# SController-8833.net
KiCad netlist of a schematic drawn in EAGLE
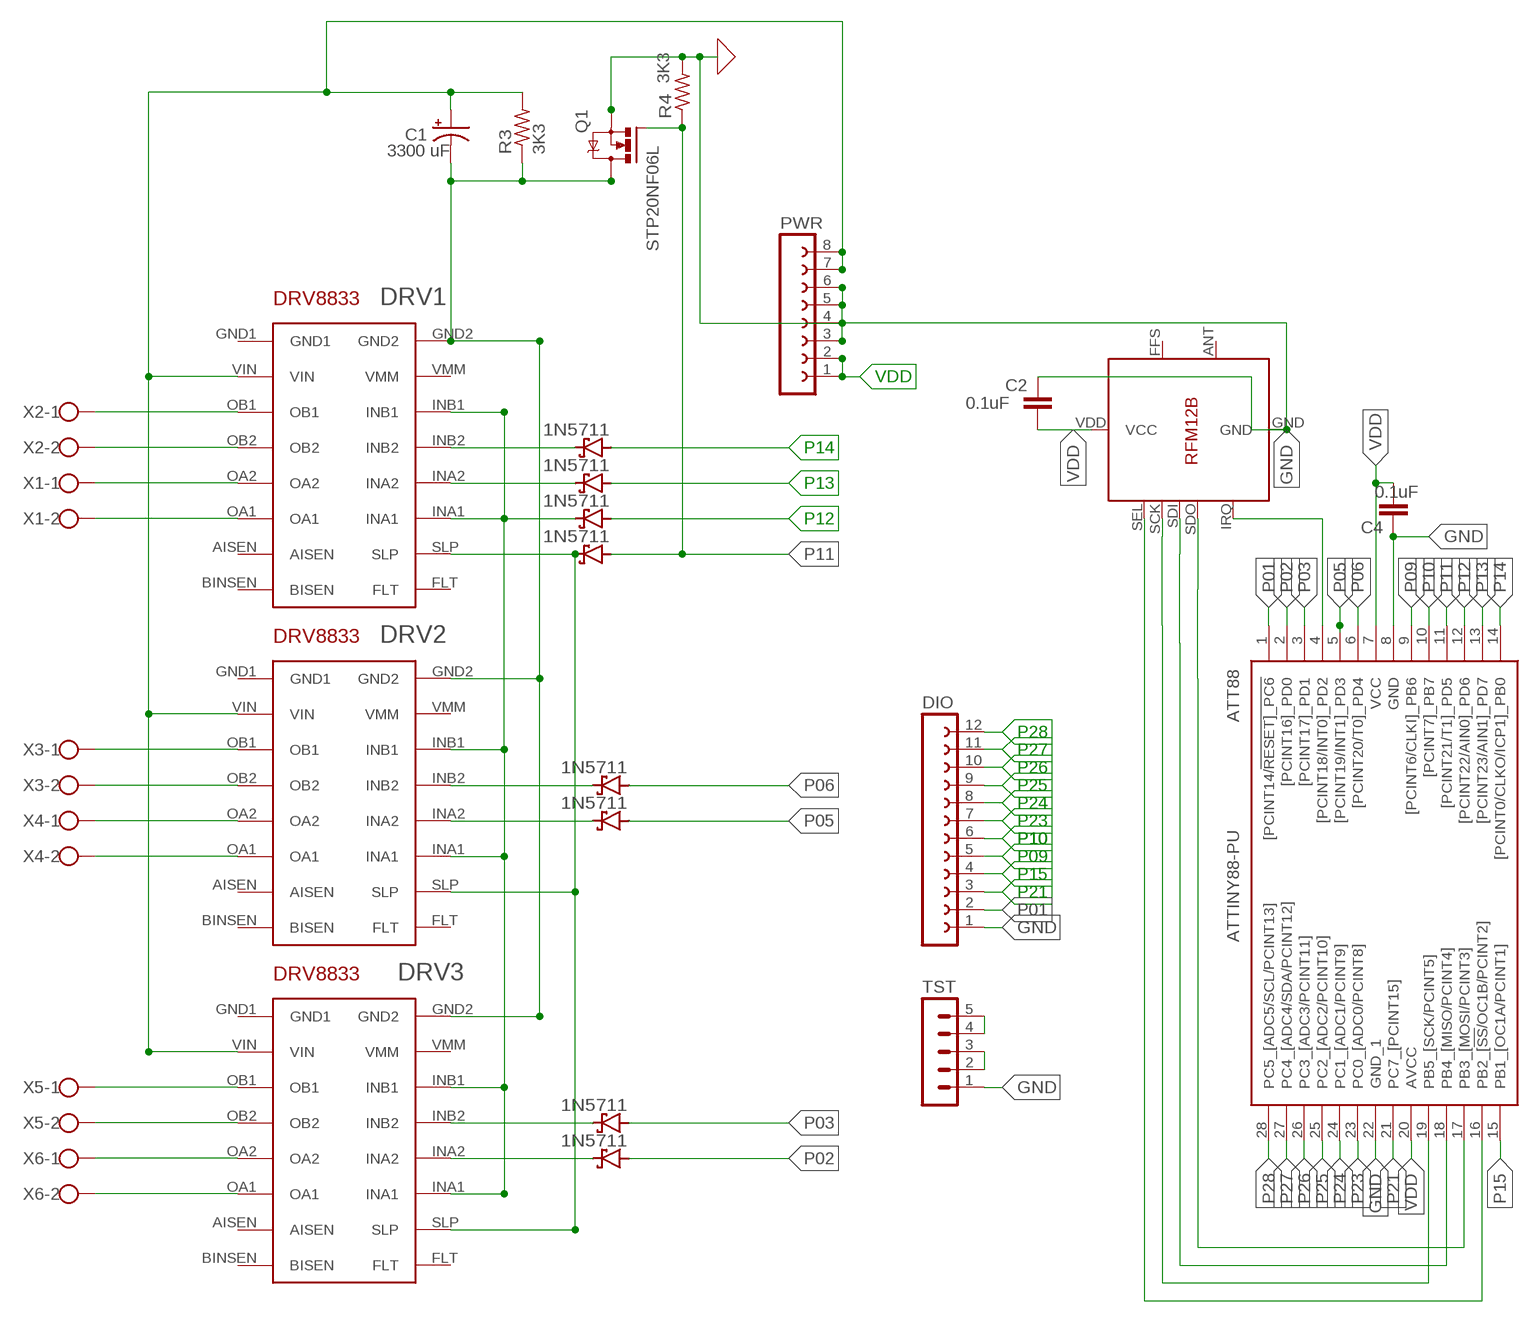
[diagram p0: schematic, sheet 1]

(export (version "E")
  (design (tool "Eeschema 10.0.6"))
  (components
    (comp (ref "1")
      (value "DRV1")
      (footprint "eagle-import:POLOLU-DRV8833")
      (libsource (lib "eagle-import") (part "POLOLU-DRV8833"))
    )
    (comp (ref "2")
      (value "DRV2")
      (footprint "eagle-import:POLOLU-DRV8833")
      (libsource (lib "eagle-import") (part "POLOLU-DRV8833"))
    )
    (comp (ref "3")
      (value "DRV3")
      (footprint "eagle-import:POLOLU-DRV8833")
      (libsource (lib "eagle-import") (part "POLOLU-DRV8833"))
    )
    (comp (ref "ATT88")
      (value "ATTINY88-PU")
      (footprint "eagle-import:DIP794W53P254L3467H457Q28N")
      (fields (field (name "MOUSER_PART_NUMBER") "556-ATTINY88-PU") (field (name "RS_PART_NUMBER") "6962406"))
      (libsource (lib "eagle-import") (part "ATTINY88-PU"))
    )
    (comp (ref "C1")
      (value "3300 uF")
      (footprint "eagle-import:E5-10,5")
      (libsource (lib "eagle-import") (part "CPOL-USE5-10.5"))
    )
    (comp (ref "C2")
      (value "0.1uF")
      (footprint "eagle-import:C2.5-2")
      (libsource (lib "eagle-import") (part "C2.5/2"))
    )
    (comp (ref "C4")
      (value "0.1uF")
      (footprint "eagle-import:C2.5-2")
      (libsource (lib "eagle-import") (part "C2.5/2"))
    )
    (comp (ref "D1")
      (value "1N5711")
      (footprint "eagle-import:F126Z12")
      (libsource (lib "eagle-import") (part "SCHOTTKY-DIODEF126Z12"))
    )
    (comp (ref "D2")
      (value "1N5711")
      (footprint "eagle-import:F126Z12")
      (libsource (lib "eagle-import") (part "SCHOTTKY-DIODEF126Z12"))
    )
    (comp (ref "D3")
      (value "1N5711")
      (footprint "eagle-import:F126Z12")
      (libsource (lib "eagle-import") (part "SCHOTTKY-DIODEF126Z12"))
    )
    (comp (ref "D4")
      (value "1N5711")
      (footprint "eagle-import:F126Z12")
      (libsource (lib "eagle-import") (part "SCHOTTKY-DIODEF126Z12"))
    )
    (comp (ref "D5")
      (value "1N5711")
      (footprint "eagle-import:F126Z12")
      (libsource (lib "eagle-import") (part "SCHOTTKY-DIODEF126Z12"))
    )
    (comp (ref "D6")
      (value "1N5711")
      (footprint "eagle-import:F126Z12")
      (libsource (lib "eagle-import") (part "SCHOTTKY-DIODEF126Z12"))
    )
    (comp (ref "D7")
      (value "1N5711")
      (footprint "eagle-import:F126Z12")
      (libsource (lib "eagle-import") (part "SCHOTTKY-DIODEF126Z12"))
    )
    (comp (ref "D8")
      (value "1N5711")
      (footprint "eagle-import:F126Z12")
      (libsource (lib "eagle-import") (part "SCHOTTKY-DIODEF126Z12"))
    )
    (comp (ref "DIO")
      (value "FE12-1")
      (footprint "eagle-import:FE12")
      (libsource (lib "eagle-import") (part "FE12-1"))
    )
    (comp (ref "PWR")
      (value "FE08-1")
      (footprint "eagle-import:FE08")
      (libsource (lib "eagle-import") (part "FE08-1"))
    )
    (comp (ref "Q1")
      (value "STP20NF06L")
      (footprint "eagle-import:TO220BV")
      (libsource (lib "eagle-import") (part "IRF540"))
    )
    (comp (ref "R3")
      (value "3K3")
      (footprint "eagle-import:0204_7")
      (libsource (lib "eagle-import") (part "R-US_0204/7"))
    )
    (comp (ref "R4")
      (value "3K3")
      (footprint "eagle-import:0204_7")
      (fields (field (name "SPICEPREFIX") "3K3"))
      (libsource (lib "eagle-import") (part "R-US_0204/7"))
    )
    (comp (ref "RFM69CW")
      (value "RFM69CW")
      (footprint "eagle-import:RFM12B")
      (libsource (lib "eagle-import") (part "RFM12B"))
    )
    (comp (ref "TST")
      (value "MA05-1")
      (footprint "eagle-import:MA05-1")
      (libsource (lib "eagle-import") (part "MA05-1"))
    )
    (comp (ref "X1")
      (value "W237-102")
      (footprint "eagle-import:W237-102")
      (fields (field (name "MPN") "237-102"))
      (libsource (lib "eagle-import") (part "W237-102"))
    )
    (comp (ref "X2")
      (value "W237-102")
      (footprint "eagle-import:W237-102")
      (fields (field (name "MPN") "237-102"))
      (libsource (lib "eagle-import") (part "W237-102"))
    )
    (comp (ref "X3")
      (value "W237-102")
      (footprint "eagle-import:W237-102")
      (fields (field (name "MPN") "237-102"))
      (libsource (lib "eagle-import") (part "W237-102"))
    )
    (comp (ref "X4")
      (value "W237-102")
      (footprint "eagle-import:W237-102")
      (fields (field (name "MPN") "237-102"))
      (libsource (lib "eagle-import") (part "W237-102"))
    )
    (comp (ref "X5")
      (value "W237-102")
      (footprint "eagle-import:W237-102")
      (fields (field (name "MPN") "237-102"))
      (libsource (lib "eagle-import") (part "W237-102"))
    )
    (comp (ref "X6")
      (value "W237-102")
      (footprint "eagle-import:W237-102")
      (fields (field (name "MPN") "237-102"))
      (libsource (lib "eagle-import") (part "W237-102"))
    )
  )
  (nets
    (net (code "1") (name "GND") (class "Default")
      (node (ref "ATT88") (pin "22") (pinfunction "GND_1_22") (pintype "power_in"))
      (node (ref "ATT88") (pin "8") (pinfunction "GND_8") (pintype "power_in"))
      (node (ref "C2") (pin "2") (pinfunction "2_2") (pintype "passive"))
      (node (ref "C4") (pin "1") (pinfunction "1_1") (pintype "passive"))
      (node (ref "DIO") (pin "1") (pinfunction "1_1") (pintype "passive"))
      (node (ref "PWR") (pin "3") (pinfunction "3_3") (pintype "passive"))
      (node (ref "PWR") (pin "4") (pinfunction "4_4") (pintype "passive"))
      (node (ref "PWR") (pin "5") (pinfunction "5_5") (pintype "passive"))
      (node (ref "PWR") (pin "6") (pinfunction "6_6") (pintype "passive"))
      (node (ref "Q1") (pin "S") (pinfunction "S_S") (pintype "passive"))
      (node (ref "R4") (pin "2") (pinfunction "2_2") (pintype "passive"))
      (node (ref "RFM69CW") (pin "GND") (pinfunction "GND_GND") (pintype "power_in"))
      (node (ref "TST") (pin "1") (pinfunction "1_1") (pintype "passive"))
    )
    (net (code "2") (name "Net-(1-PadGND2)") (class "Default")
      (node (ref "1") (pin "GND2") (pinfunction "GND2_GND2") (pintype "bidirectional"))
      (node (ref "2") (pin "GND2") (pinfunction "GND2_GND2") (pintype "bidirectional"))
      (node (ref "3") (pin "GND2") (pinfunction "GND2_GND2") (pintype "bidirectional"))
      (node (ref "C1") (pin "-") (pinfunction "-_-") (pintype "passive"))
      (node (ref "Q1") (pin "D") (pinfunction "D_D") (pintype "passive"))
      (node (ref "R3") (pin "1") (pinfunction "1_1") (pintype "passive"))
    )
    (net (code "3") (name "Net-(1-PadINA1)") (class "Default")
      (node (ref "1") (pin "INA1") (pinfunction "INA1_INA1") (pintype "bidirectional"))
      (node (ref "1") (pin "INB1") (pinfunction "INB1_INB1") (pintype "bidirectional"))
      (node (ref "2") (pin "INA1") (pinfunction "INA1_INA1") (pintype "bidirectional"))
      (node (ref "2") (pin "INB1") (pinfunction "INB1_INB1") (pintype "bidirectional"))
      (node (ref "3") (pin "INA1") (pinfunction "INA1_INA1") (pintype "bidirectional"))
      (node (ref "3") (pin "INB1") (pinfunction "INB1_INB1") (pintype "bidirectional"))
      (node (ref "D3") (pin "C") (pinfunction "C_C") (pintype "passive"))
    )
    (net (code "4") (name "Net-(1-PadINA2)") (class "Default")
      (node (ref "1") (pin "INA2") (pinfunction "INA2_INA2") (pintype "bidirectional"))
      (node (ref "D2") (pin "C") (pinfunction "C_C") (pintype "passive"))
    )
    (net (code "5") (name "Net-(1-PadINB2)") (class "Default")
      (node (ref "1") (pin "INB2") (pinfunction "INB2_INB2") (pintype "bidirectional"))
      (node (ref "D1") (pin "C") (pinfunction "C_C") (pintype "passive"))
    )
    (net (code "6") (name "Net-(1-PadSLP)") (class "Default")
      (node (ref "1") (pin "SLP") (pinfunction "SLP_SLP") (pintype "bidirectional"))
      (node (ref "2") (pin "SLP") (pinfunction "SLP_SLP") (pintype "bidirectional"))
      (node (ref "3") (pin "SLP") (pinfunction "SLP_SLP") (pintype "bidirectional"))
      (node (ref "D4") (pin "C") (pinfunction "C_C") (pintype "passive"))
    )
    (net (code "7") (name "Net-(1-PadVIN)") (class "Default")
      (node (ref "1") (pin "VIN") (pinfunction "VIN_VIN") (pintype "bidirectional"))
      (node (ref "2") (pin "VIN") (pinfunction "VIN_VIN") (pintype "bidirectional"))
      (node (ref "3") (pin "VIN") (pinfunction "VIN_VIN") (pintype "bidirectional"))
      (node (ref "C1") (pin "+") (pinfunction "+_+") (pintype "passive"))
      (node (ref "PWR") (pin "7") (pinfunction "7_7") (pintype "passive"))
      (node (ref "PWR") (pin "8") (pinfunction "8_8") (pintype "passive"))
      (node (ref "R3") (pin "2") (pinfunction "2_2") (pintype "passive"))
    )
    (net (code "8") (name "Net-(2-PadINA2)") (class "Default")
      (node (ref "2") (pin "INA2") (pinfunction "INA2_INA2") (pintype "bidirectional"))
      (node (ref "D6") (pin "C") (pinfunction "C_C") (pintype "passive"))
    )
    (net (code "9") (name "Net-(2-PadINB2)") (class "Default")
      (node (ref "2") (pin "INB2") (pinfunction "INB2_INB2") (pintype "bidirectional"))
      (node (ref "D5") (pin "C") (pinfunction "C_C") (pintype "passive"))
    )
    (net (code "10") (name "Net-(3-PadINA2)") (class "Default")
      (node (ref "3") (pin "INA2") (pinfunction "INA2_INA2") (pintype "bidirectional"))
      (node (ref "D8") (pin "C") (pinfunction "C_C") (pintype "passive"))
    )
    (net (code "11") (name "Net-(3-PadINB2)") (class "Default")
      (node (ref "3") (pin "INB2") (pinfunction "INB2_INB2") (pintype "bidirectional"))
      (node (ref "D7") (pin "C") (pinfunction "C_C") (pintype "passive"))
    )
    (net (code "12") (name "Net-(ATT88-PB2_[~{SS}{slash}OC1B{slash}PCINT2])") (class "Default")
      (node (ref "ATT88") (pin "16") (pinfunction "PB2_[~{SS}/OC1B/PCINT2]_16") (pintype "bidirectional"))
      (node (ref "RFM69CW") (pin "SEL") (pinfunction "SEL_SEL") (pintype "input"))
    )
    (net (code "13") (name "Net-(ATT88-PB3_[MOSI{slash}PCINT3])") (class "Default")
      (node (ref "ATT88") (pin "17") (pinfunction "PB3_[MOSI/PCINT3]_17") (pintype "bidirectional"))
      (node (ref "RFM69CW") (pin "SDO") (pinfunction "SDO_SDO") (pintype "output"))
    )
    (net (code "14") (name "Net-(ATT88-PB4_[MISO{slash}PCINT4])") (class "Default")
      (node (ref "ATT88") (pin "18") (pinfunction "PB4_[MISO/PCINT4]_18") (pintype "bidirectional"))
      (node (ref "RFM69CW") (pin "SDI") (pinfunction "SDI_SDI") (pintype "input"))
    )
    (net (code "15") (name "Net-(ATT88-PB5_[SCK{slash}PCINT5])") (class "Default")
      (node (ref "ATT88") (pin "19") (pinfunction "PB5_[SCK/PCINT5]_19") (pintype "bidirectional"))
      (node (ref "RFM69CW") (pin "SCK") (pinfunction "SCK_SCK") (pintype "input"))
    )
    (net (code "16") (name "Net-(ATT88-[PCINT18{slash}INT0]_PD2)") (class "Default")
      (node (ref "ATT88") (pin "4") (pinfunction "[PCINT18/INT0]_PD2_4") (pintype "bidirectional"))
      (node (ref "RFM69CW") (pin "IRQ") (pinfunction "IRQ_IRQ") (pintype "open_collector"))
    )
    (net (code "17") (name "Net-(TST-Pad2)") (class "Default")
      (node (ref "TST") (pin "2") (pinfunction "2_2") (pintype "passive"))
      (node (ref "TST") (pin "3") (pinfunction "3_3") (pintype "passive"))
    )
    (net (code "18") (name "Net-(TST-Pad4)") (class "Default")
      (node (ref "TST") (pin "4") (pinfunction "4_4") (pintype "passive"))
      (node (ref "TST") (pin "5") (pinfunction "5_5") (pintype "passive"))
    )
    (net (code "19") (name "Net-(X1A-KL)") (class "Default")
      (node (ref "1") (pin "OA2") (pinfunction "OA2_OA2") (pintype "bidirectional"))
      (node (ref "X1") (pin "1") (pinfunction "KL_1") (pintype "passive"))
    )
    (net (code "20") (name "Net-(X1B-KL)") (class "Default")
      (node (ref "1") (pin "OA1") (pinfunction "OA1_OA1") (pintype "bidirectional"))
      (node (ref "X1") (pin "2") (pinfunction "KL_2") (pintype "passive"))
    )
    (net (code "21") (name "Net-(X2A-KL)") (class "Default")
      (node (ref "1") (pin "OB1") (pinfunction "OB1_OB1") (pintype "bidirectional"))
      (node (ref "X2") (pin "1") (pinfunction "KL_1") (pintype "passive"))
    )
    (net (code "22") (name "Net-(X2B-KL)") (class "Default")
      (node (ref "1") (pin "OB2") (pinfunction "OB2_OB2") (pintype "bidirectional"))
      (node (ref "X2") (pin "2") (pinfunction "KL_2") (pintype "passive"))
    )
    (net (code "23") (name "Net-(X3A-KL)") (class "Default")
      (node (ref "2") (pin "OB1") (pinfunction "OB1_OB1") (pintype "bidirectional"))
      (node (ref "X3") (pin "1") (pinfunction "KL_1") (pintype "passive"))
    )
    (net (code "24") (name "Net-(X3B-KL)") (class "Default")
      (node (ref "2") (pin "OB2") (pinfunction "OB2_OB2") (pintype "bidirectional"))
      (node (ref "X3") (pin "2") (pinfunction "KL_2") (pintype "passive"))
    )
    (net (code "25") (name "Net-(X4A-KL)") (class "Default")
      (node (ref "2") (pin "OA2") (pinfunction "OA2_OA2") (pintype "bidirectional"))
      (node (ref "X4") (pin "1") (pinfunction "KL_1") (pintype "passive"))
    )
    (net (code "26") (name "Net-(X4B-KL)") (class "Default")
      (node (ref "2") (pin "OA1") (pinfunction "OA1_OA1") (pintype "bidirectional"))
      (node (ref "X4") (pin "2") (pinfunction "KL_2") (pintype "passive"))
    )
    (net (code "27") (name "Net-(X5A-KL)") (class "Default")
      (node (ref "3") (pin "OB1") (pinfunction "OB1_OB1") (pintype "bidirectional"))
      (node (ref "X5") (pin "1") (pinfunction "KL_1") (pintype "passive"))
    )
    (net (code "28") (name "Net-(X5B-KL)") (class "Default")
      (node (ref "3") (pin "OB2") (pinfunction "OB2_OB2") (pintype "bidirectional"))
      (node (ref "X5") (pin "2") (pinfunction "KL_2") (pintype "passive"))
    )
    (net (code "29") (name "Net-(X6A-KL)") (class "Default")
      (node (ref "3") (pin "OA2") (pinfunction "OA2_OA2") (pintype "bidirectional"))
      (node (ref "X6") (pin "1") (pinfunction "KL_1") (pintype "passive"))
    )
    (net (code "30") (name "Net-(X6B-KL)") (class "Default")
      (node (ref "3") (pin "OA1") (pinfunction "OA1_OA1") (pintype "bidirectional"))
      (node (ref "X6") (pin "2") (pinfunction "KL_2") (pintype "passive"))
    )
    (net (code "31") (name "P01") (class "Default")
      (node (ref "ATT88") (pin "1") (pinfunction "[PCINT14/~{RESET]_PC6}_1") (pintype "bidirectional"))
      (node (ref "DIO") (pin "2") (pinfunction "2_2") (pintype "passive"))
    )
    (net (code "32") (name "P02") (class "Default")
      (node (ref "ATT88") (pin "2") (pinfunction "[PCINT16]_PD0_2") (pintype "bidirectional"))
      (node (ref "D8") (pin "A") (pinfunction "A_A") (pintype "passive"))
    )
    (net (code "33") (name "P03") (class "Default")
      (node (ref "ATT88") (pin "3") (pinfunction "[PCINT17]_PD1_3") (pintype "bidirectional"))
      (node (ref "D7") (pin "A") (pinfunction "A_A") (pintype "passive"))
    )
    (net (code "34") (name "P05") (class "Default")
      (node (ref "ATT88") (pin "5") (pinfunction "[PCINT19/INT1]_PD3_5") (pintype "bidirectional"))
      (node (ref "D6") (pin "A") (pinfunction "A_A") (pintype "passive"))
    )
    (net (code "35") (name "P06") (class "Default")
      (node (ref "ATT88") (pin "6") (pinfunction "[PCINT20/T0]_PD4_6") (pintype "bidirectional"))
      (node (ref "D5") (pin "A") (pinfunction "A_A") (pintype "passive"))
    )
    (net (code "36") (name "P09") (class "Default")
      (node (ref "ATT88") (pin "9") (pinfunction "[PCINT6/CLKI]_PB6_9") (pintype "bidirectional"))
      (node (ref "DIO") (pin "5") (pinfunction "5_5") (pintype "passive"))
    )
    (net (code "37") (name "P10") (class "Default")
      (node (ref "ATT88") (pin "10") (pinfunction "[PCINT7]_PB7_10") (pintype "bidirectional"))
      (node (ref "DIO") (pin "6") (pinfunction "6_6") (pintype "passive"))
    )
    (net (code "38") (name "P11") (class "Default")
      (node (ref "ATT88") (pin "11") (pinfunction "[PCINT21/T1]_PD5_11") (pintype "bidirectional"))
      (node (ref "D4") (pin "A") (pinfunction "A_A") (pintype "passive"))
      (node (ref "Q1") (pin "G") (pinfunction "G_G") (pintype "passive"))
      (node (ref "R4") (pin "1") (pinfunction "1_1") (pintype "passive"))
    )
    (net (code "39") (name "P12") (class "Default")
      (node (ref "ATT88") (pin "12") (pinfunction "[PCINT22/AIN0]_PD6_12") (pintype "bidirectional"))
      (node (ref "D3") (pin "A") (pinfunction "A_A") (pintype "passive"))
    )
    (net (code "40") (name "P13") (class "Default")
      (node (ref "ATT88") (pin "13") (pinfunction "[PCINT23/AIN1]_PD7_13") (pintype "bidirectional"))
      (node (ref "D2") (pin "A") (pinfunction "A_A") (pintype "passive"))
    )
    (net (code "41") (name "P14") (class "Default")
      (node (ref "ATT88") (pin "14") (pinfunction "[PCINT0/CLKO/ICP1]_PB0_14") (pintype "bidirectional"))
      (node (ref "D1") (pin "A") (pinfunction "A_A") (pintype "passive"))
    )
    (net (code "42") (name "P15") (class "Default")
      (node (ref "ATT88") (pin "15") (pinfunction "PB1_[OC1A/PCINT1]_15") (pintype "bidirectional"))
      (node (ref "DIO") (pin "4") (pinfunction "4_4") (pintype "passive"))
    )
    (net (code "43") (name "P21") (class "Default")
      (node (ref "ATT88") (pin "21") (pinfunction "PC7_[PCINT15]_21") (pintype "bidirectional"))
      (node (ref "DIO") (pin "3") (pinfunction "3_3") (pintype "passive"))
    )
    (net (code "44") (name "P23") (class "Default")
      (node (ref "ATT88") (pin "23") (pinfunction "PC0_[ADC0/PCINT8]_23") (pintype "bidirectional"))
      (node (ref "DIO") (pin "7") (pinfunction "7_7") (pintype "passive"))
    )
    (net (code "45") (name "P24") (class "Default")
      (node (ref "ATT88") (pin "24") (pinfunction "PC1_[ADC1/PCINT9]_24") (pintype "bidirectional"))
      (node (ref "DIO") (pin "8") (pinfunction "8_8") (pintype "passive"))
    )
    (net (code "46") (name "P25") (class "Default")
      (node (ref "ATT88") (pin "25") (pinfunction "PC2_[ADC2/PCINT10]_25") (pintype "bidirectional"))
      (node (ref "DIO") (pin "9") (pinfunction "9_9") (pintype "passive"))
    )
    (net (code "47") (name "P26") (class "Default")
      (node (ref "ATT88") (pin "26") (pinfunction "PC3_[ADC3/PCINT11]_26") (pintype "bidirectional"))
      (node (ref "DIO") (pin "10") (pinfunction "10_10") (pintype "passive"))
    )
    (net (code "48") (name "P27") (class "Default")
      (node (ref "ATT88") (pin "27") (pinfunction "PC4_[ADC4/SDA/PCINT12]_27") (pintype "bidirectional"))
      (node (ref "DIO") (pin "11") (pinfunction "11_11") (pintype "passive"))
    )
    (net (code "49") (name "P28") (class "Default")
      (node (ref "ATT88") (pin "28") (pinfunction "PC5_[ADC5/SCL/PCINT13]_28") (pintype "bidirectional"))
      (node (ref "DIO") (pin "12") (pinfunction "12_12") (pintype "passive"))
    )
    (net (code "50") (name "VDD") (class "Default")
      (node (ref "ATT88") (pin "20") (pinfunction "AVCC_20") (pintype "power_in"))
      (node (ref "ATT88") (pin "7") (pinfunction "VCC_7") (pintype "power_in"))
      (node (ref "C2") (pin "1") (pinfunction "1_1") (pintype "passive"))
      (node (ref "C4") (pin "2") (pinfunction "2_2") (pintype "passive"))
      (node (ref "PWR") (pin "1") (pinfunction "1_1") (pintype "passive"))
      (node (ref "PWR") (pin "2") (pinfunction "2_2") (pintype "passive"))
      (node (ref "RFM69CW") (pin "VDD") (pinfunction "VCC_VDD") (pintype "power_in"))
    )
    (net (code "51") (name "unconnected-(1-BISEN-PadBINSEN)") (class "Default")
      (node (ref "1") (pin "BINSEN") (pinfunction "BISEN_BINSEN") (pintype "bidirectional"))
    )
    (net (code "52") (name "unconnected-(1-PadAISEN)") (class "Default")
      (node (ref "1") (pin "AISEN") (pinfunction "AISEN_AISEN") (pintype "bidirectional"))
    )
    (net (code "53") (name "unconnected-(1-PadFLT)") (class "Default")
      (node (ref "1") (pin "FLT") (pinfunction "FLT_FLT") (pintype "bidirectional"))
    )
    (net (code "54") (name "unconnected-(1-PadGND1)") (class "Default")
      (node (ref "1") (pin "GND1") (pinfunction "GND1_GND1") (pintype "bidirectional"))
    )
    (net (code "55") (name "unconnected-(1-PadVMM)") (class "Default")
      (node (ref "1") (pin "VMM") (pinfunction "VMM_VMM") (pintype "output"))
    )
    (net (code "56") (name "unconnected-(2-BISEN-PadBINSEN)") (class "Default")
      (node (ref "2") (pin "BINSEN") (pinfunction "BISEN_BINSEN") (pintype "bidirectional"))
    )
    (net (code "57") (name "unconnected-(2-PadAISEN)") (class "Default")
      (node (ref "2") (pin "AISEN") (pinfunction "AISEN_AISEN") (pintype "bidirectional"))
    )
    (net (code "58") (name "unconnected-(2-PadFLT)") (class "Default")
      (node (ref "2") (pin "FLT") (pinfunction "FLT_FLT") (pintype "bidirectional"))
    )
    (net (code "59") (name "unconnected-(2-PadGND1)") (class "Default")
      (node (ref "2") (pin "GND1") (pinfunction "GND1_GND1") (pintype "bidirectional"))
    )
    (net (code "60") (name "unconnected-(2-PadVMM)") (class "Default")
      (node (ref "2") (pin "VMM") (pinfunction "VMM_VMM") (pintype "output"))
    )
    (net (code "61") (name "unconnected-(3-BISEN-PadBINSEN)") (class "Default")
      (node (ref "3") (pin "BINSEN") (pinfunction "BISEN_BINSEN") (pintype "bidirectional"))
    )
    (net (code "62") (name "unconnected-(3-PadAISEN)") (class "Default")
      (node (ref "3") (pin "AISEN") (pinfunction "AISEN_AISEN") (pintype "bidirectional"))
    )
    (net (code "63") (name "unconnected-(3-PadFLT)") (class "Default")
      (node (ref "3") (pin "FLT") (pinfunction "FLT_FLT") (pintype "bidirectional"))
    )
    (net (code "64") (name "unconnected-(3-PadGND1)") (class "Default")
      (node (ref "3") (pin "GND1") (pinfunction "GND1_GND1") (pintype "bidirectional"))
    )
    (net (code "65") (name "unconnected-(3-PadVMM)") (class "Default")
      (node (ref "3") (pin "VMM") (pinfunction "VMM_VMM") (pintype "output"))
    )
    (net (code "66") (name "unconnected-(RFM69CW-PadANT)") (class "Default")
      (node (ref "RFM69CW") (pin "ANT") (pinfunction "ANT_ANT") (pintype "passive"))
    )
    (net (code "67") (name "unconnected-(RFM69CW-PadFFS)") (class "Default")
      (node (ref "RFM69CW") (pin "FFS") (pinfunction "FFS_FFS") (pintype "bidirectional"))
    )
  )
)
